# 6_Motor_Control.net
KiCad netlist of a schematic drawn in Altium Designer
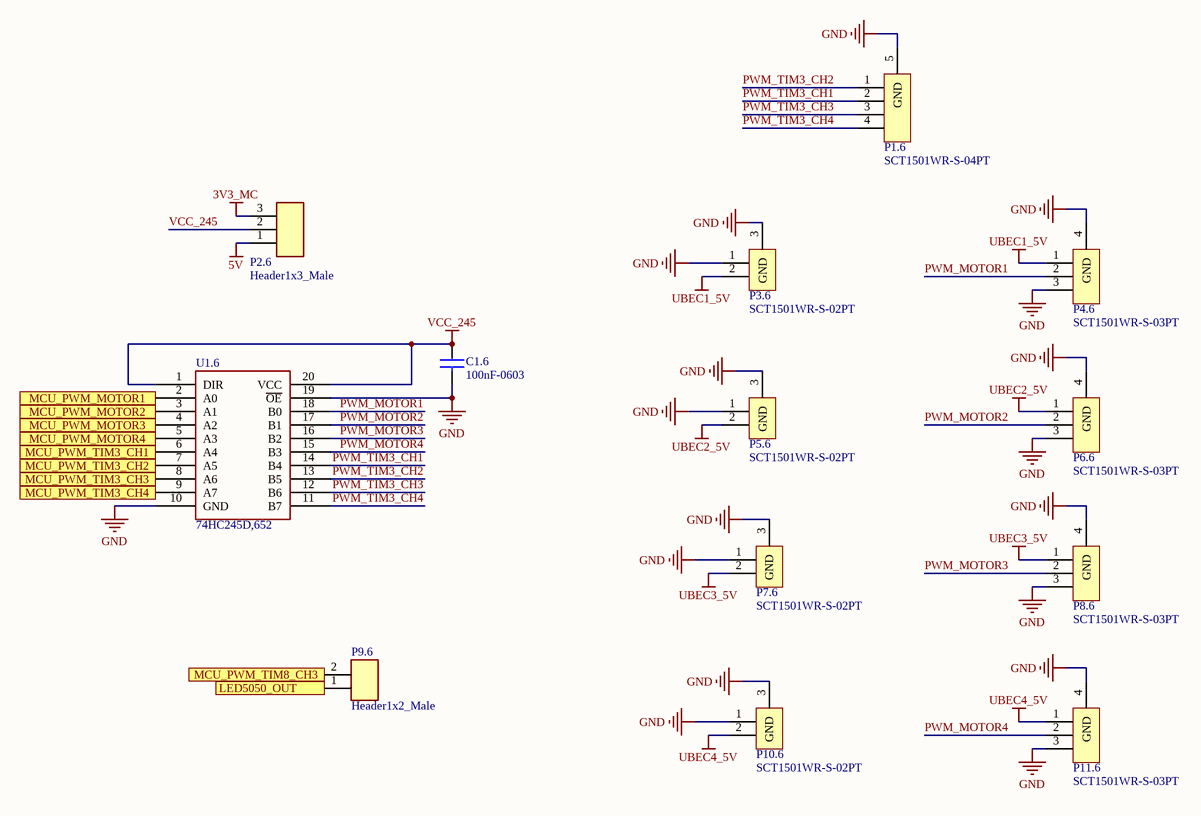
[diagram p0: [6] Motor_Control.SchDoc]

(export (version "E")
  (design (tool "Eeschema 10.0.6"))
  (components
    (comp (ref "C1.6")
      (value "100nF-0603")
      (footprint "CAP0603")
      (description "CAP CER 0.1UF 50V X7R 0603")
      (fields (field (name "TOLERANCE") "±10%"))
      (libsource (lib "Minh_Lib") (part "CC0603KRX7R9BB104"))
    )
    (comp (ref "P1.6")
      (value "SCT1501WR-S-04PT")
      (footprint "Connector ZH1.5 4P SMD")
      (libsource (lib "Minh_Lib") (part "SCT1501WR-S-04PT"))
    )
    (comp (ref "P2.6")
      (value "Header1x3_Male")
      (footprint "Minh_Lib:HDR1x3_2.54_MALE")
      (description "Header1x3_2.54_MALE")
      (libsource (lib "Minh_Lib") (part "HDR1x3_2.54_MALE"))
    )
    (comp (ref "P3.6")
      (value "SCT1501WR-S-02PT")
      (footprint "Connector ZH1.5 2P SMD")
      (libsource (lib "Minh_Lib") (part "SCT1501WR-S-02PT"))
    )
    (comp (ref "P4.6")
      (value "SCT1501WR-S-03PT")
      (footprint "Connector ZH1.5 3P SMD")
      (libsource (lib "Minh_Lib") (part "SCT1501WR-S-03PT"))
    )
    (comp (ref "P5.6")
      (value "SCT1501WR-S-02PT")
      (footprint "Connector ZH1.5 2P SMD")
      (libsource (lib "Minh_Lib") (part "SCT1501WR-S-02PT"))
    )
    (comp (ref "P6.6")
      (value "SCT1501WR-S-03PT")
      (footprint "Connector ZH1.5 3P SMD")
      (libsource (lib "Minh_Lib") (part "SCT1501WR-S-03PT"))
    )
    (comp (ref "P7.6")
      (value "SCT1501WR-S-02PT")
      (footprint "Connector ZH1.5 2P SMD")
      (libsource (lib "Minh_Lib") (part "SCT1501WR-S-02PT"))
    )
    (comp (ref "P8.6")
      (value "SCT1501WR-S-03PT")
      (footprint "Connector ZH1.5 3P SMD")
      (libsource (lib "Minh_Lib") (part "SCT1501WR-S-03PT"))
    )
    (comp (ref "P9.6")
      (value "Header1x2_Male")
      (footprint "Minh_Lib:HDR1x2_2.54_MALE")
      (description "Header1x2_2.54_MALE")
      (libsource (lib "Minh_Lib") (part "HDR1x2_2.54_MALE"))
    )
    (comp (ref "P10.6")
      (value "SCT1501WR-S-02PT")
      (footprint "Connector ZH1.5 2P SMD")
      (libsource (lib "Minh_Lib") (part "SCT1501WR-S-02PT"))
    )
    (comp (ref "P11.6")
      (value "SCT1501WR-S-03PT")
      (footprint "Connector ZH1.5 3P SMD")
      (libsource (lib "Minh_Lib") (part "SCT1501WR-S-03PT"))
    )
    (comp (ref "U1.6")
      (value "74HC245D,652")
      (footprint "SOT163-1_NEX")
      (fields (field (name "COPYRIGHT") "Copyright (C) 2016 Accelerated Designs. All rights reserved"))
      (libsource (lib "Minh_Lib") (part "74HC245D,652"))
    )
  )
  (nets
    (net (code "1") (name "/LED5050_OUT") (class "Default")
      (node (ref "P9.6") (pin "1") (pinfunction "1_1") (pintype "passive"))
    )
    (net (code "2") (name "/MCU_PWM_MOTOR1") (class "Default")
      (node (ref "U1.6") (pin "2") (pinfunction "A0_2") (pintype "passive"))
    )
    (net (code "3") (name "/MCU_PWM_MOTOR2") (class "Default")
      (node (ref "U1.6") (pin "3") (pinfunction "A1_3") (pintype "passive"))
    )
    (net (code "4") (name "/MCU_PWM_MOTOR3") (class "Default")
      (node (ref "U1.6") (pin "4") (pinfunction "A2_4") (pintype "passive"))
    )
    (net (code "5") (name "/MCU_PWM_MOTOR4") (class "Default")
      (node (ref "U1.6") (pin "5") (pinfunction "A3_5") (pintype "passive"))
    )
    (net (code "6") (name "/MCU_PWM_TIM3_CH1") (class "Default")
      (node (ref "U1.6") (pin "6") (pinfunction "A4_6") (pintype "passive"))
    )
    (net (code "7") (name "/MCU_PWM_TIM3_CH2") (class "Default")
      (node (ref "U1.6") (pin "7") (pinfunction "A5_7") (pintype "passive"))
    )
    (net (code "8") (name "/MCU_PWM_TIM3_CH3") (class "Default")
      (node (ref "U1.6") (pin "8") (pinfunction "A6_8") (pintype "passive"))
    )
    (net (code "9") (name "/MCU_PWM_TIM3_CH4") (class "Default")
      (node (ref "U1.6") (pin "9") (pinfunction "A7_9") (pintype "passive"))
    )
    (net (code "10") (name "/MCU_PWM_TIM8_CH3") (class "Default")
      (node (ref "P9.6") (pin "2") (pinfunction "2_2") (pintype "passive"))
    )
    (net (code "11") (name "/PWM_MOTOR1") (class "Default")
      (node (ref "P4.6") (pin "2") (pinfunction "2_2") (pintype "passive"))
      (node (ref "U1.6") (pin "18") (pinfunction "B0_18") (pintype "passive"))
    )
    (net (code "12") (name "/PWM_MOTOR2") (class "Default")
      (node (ref "P6.6") (pin "2") (pinfunction "2_2") (pintype "passive"))
      (node (ref "U1.6") (pin "17") (pinfunction "B1_17") (pintype "passive"))
    )
    (net (code "13") (name "/PWM_MOTOR3") (class "Default")
      (node (ref "P8.6") (pin "2") (pinfunction "2_2") (pintype "passive"))
      (node (ref "U1.6") (pin "16") (pinfunction "B2_16") (pintype "passive"))
    )
    (net (code "14") (name "/PWM_MOTOR4") (class "Default")
      (node (ref "P11.6") (pin "2") (pinfunction "2_2") (pintype "passive"))
      (node (ref "U1.6") (pin "15") (pinfunction "B3_15") (pintype "passive"))
    )
    (net (code "15") (name "/PWM_TIM3_CH1") (class "Default")
      (node (ref "P1.6") (pin "2") (pinfunction "2_2") (pintype "passive"))
      (node (ref "U1.6") (pin "14") (pinfunction "B4_14") (pintype "passive"))
    )
    (net (code "16") (name "/PWM_TIM3_CH2") (class "Default")
      (node (ref "P1.6") (pin "1") (pinfunction "1_1") (pintype "passive"))
      (node (ref "U1.6") (pin "13") (pinfunction "B5_13") (pintype "passive"))
    )
    (net (code "17") (name "/PWM_TIM3_CH3") (class "Default")
      (node (ref "P1.6") (pin "3") (pinfunction "3_3") (pintype "passive"))
      (node (ref "U1.6") (pin "12") (pinfunction "B6_12") (pintype "passive"))
    )
    (net (code "18") (name "/PWM_TIM3_CH4") (class "Default")
      (node (ref "P1.6") (pin "4") (pinfunction "4_4") (pintype "passive"))
      (node (ref "U1.6") (pin "11") (pinfunction "B7_11") (pintype "passive"))
    )
    (net (code "19") (name "3V3_MC") (class "Default")
      (node (ref "P2.6") (pin "3") (pinfunction "3_3") (pintype "passive"))
    )
    (net (code "20") (name "5V") (class "Default")
      (node (ref "P2.6") (pin "1") (pinfunction "1_1") (pintype "passive"))
    )
    (net (code "21") (name "GND") (class "Default")
      (node (ref "C1.6") (pin "2") (pinfunction "2_2") (pintype "passive"))
      (node (ref "P1.6") (pin "5") (pinfunction "GND_5") (pintype "passive"))
      (node (ref "P10.6") (pin "1") (pinfunction "1_1") (pintype "passive"))
      (node (ref "P10.6") (pin "3") (pinfunction "GND_3") (pintype "passive"))
      (node (ref "P11.6") (pin "3") (pinfunction "3_3") (pintype "passive"))
      (node (ref "P11.6") (pin "4") (pinfunction "GND_4") (pintype "passive"))
      (node (ref "P3.6") (pin "1") (pinfunction "1_1") (pintype "passive"))
      (node (ref "P3.6") (pin "3") (pinfunction "GND_3") (pintype "passive"))
      (node (ref "P4.6") (pin "3") (pinfunction "3_3") (pintype "passive"))
      (node (ref "P4.6") (pin "4") (pinfunction "GND_4") (pintype "passive"))
      (node (ref "P5.6") (pin "1") (pinfunction "1_1") (pintype "passive"))
      (node (ref "P5.6") (pin "3") (pinfunction "GND_3") (pintype "passive"))
      (node (ref "P6.6") (pin "3") (pinfunction "3_3") (pintype "passive"))
      (node (ref "P6.6") (pin "4") (pinfunction "GND_4") (pintype "passive"))
      (node (ref "P7.6") (pin "1") (pinfunction "1_1") (pintype "passive"))
      (node (ref "P7.6") (pin "3") (pinfunction "GND_3") (pintype "passive"))
      (node (ref "P8.6") (pin "3") (pinfunction "3_3") (pintype "passive"))
      (node (ref "P8.6") (pin "4") (pinfunction "GND_4") (pintype "passive"))
      (node (ref "U1.6") (pin "10") (pinfunction "GND_10") (pintype "passive"))
      (node (ref "U1.6") (pin "19") (pinfunction "~{OE}_19") (pintype "passive"))
    )
    (net (code "22") (name "UBEC1_5V") (class "Default")
      (node (ref "P3.6") (pin "2") (pinfunction "2_2") (pintype "passive"))
      (node (ref "P4.6") (pin "1") (pinfunction "1_1") (pintype "passive"))
    )
    (net (code "23") (name "UBEC2_5V") (class "Default")
      (node (ref "P5.6") (pin "2") (pinfunction "2_2") (pintype "passive"))
      (node (ref "P6.6") (pin "1") (pinfunction "1_1") (pintype "passive"))
    )
    (net (code "24") (name "UBEC3_5V") (class "Default")
      (node (ref "P7.6") (pin "2") (pinfunction "2_2") (pintype "passive"))
      (node (ref "P8.6") (pin "1") (pinfunction "1_1") (pintype "passive"))
    )
    (net (code "25") (name "UBEC4_5V") (class "Default")
      (node (ref "P10.6") (pin "2") (pinfunction "2_2") (pintype "passive"))
      (node (ref "P11.6") (pin "1") (pinfunction "1_1") (pintype "passive"))
    )
    (net (code "26") (name "VCC_245") (class "Default")
      (node (ref "C1.6") (pin "1") (pinfunction "1_1") (pintype "passive"))
      (node (ref "P2.6") (pin "2") (pinfunction "2_2") (pintype "passive"))
      (node (ref "U1.6") (pin "1") (pinfunction "DIR_1") (pintype "passive"))
      (node (ref "U1.6") (pin "20") (pinfunction "VCC_20") (pintype "passive"))
    )
  )
)
